# Sheet1.net
KiCad netlist of a schematic drawn in Altium Designer
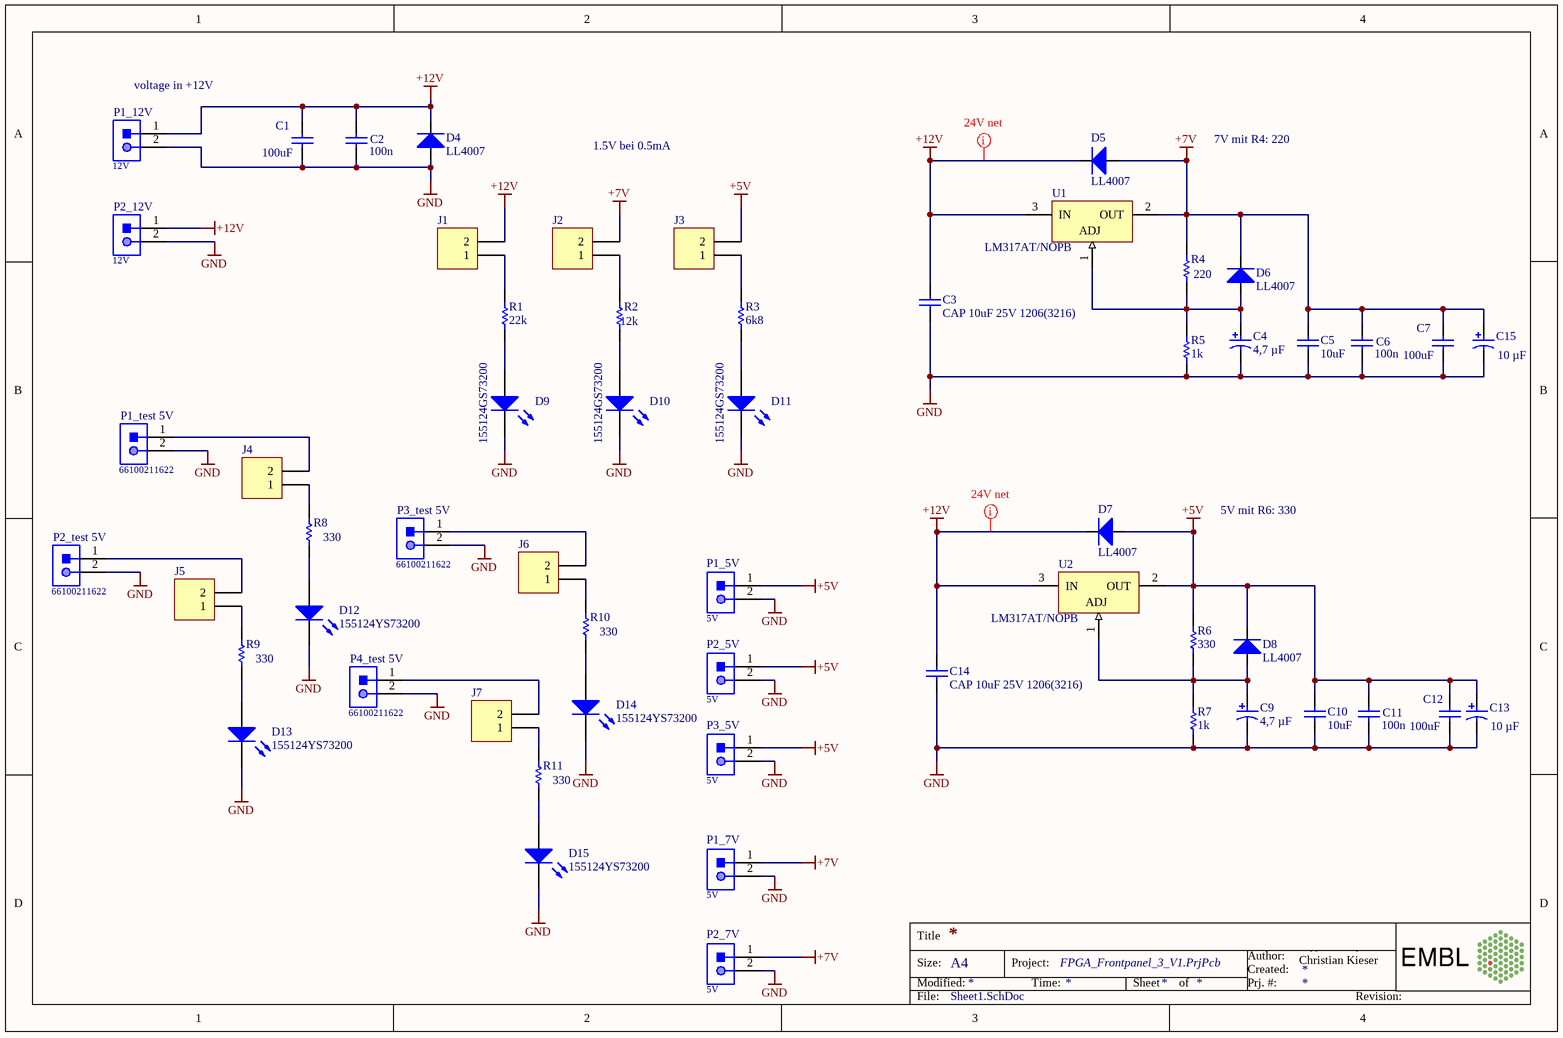
[diagram p0: Sheet1.SchDoc]

(export (version "E")
  (design (tool "Eeschema 10.0.6"))
  (components
    (comp (ref "C1")
      (value "100uF")
      (footprint "CAPC1206(3216)190_L")
      (description "CAP 100uF 6.3V ±20% 1206 (3216 Metric) Thickness 1.9mm SMD")
      (fields (field (name "TOLERANCE") "Â±20%") (field (name "PARTNUMBER") "885012108005"))
      (libsource (lib "Altium Vault EMBL 3") (part "CMP-00469-2"))
    )
    (comp (ref "C2")
      (value "100n")
      (footprint "CAPC2013X88X50ML20T25")
      (description "generic 0805 COG oder X7R Vielschichtkondensatoren max. +/-10%")
      (libsource (lib "Altium Vault EMBL 3") (part "CMP-001-0082-2"))
    )
    (comp (ref "C3")
      (value "CAP 10uF 25V 1206(3216)")
      (footprint "CAPC1206(3216)190_N")
      (description "CAP 10uF 25V -20% to +80% 1206 (3216 Metric) Thickness 1.9mm SMD")
      (fields
        (field (name "TOLERANCE") "-20% to +80%")
        (field (name "MANUFACTURER") "Wurth Electronics Inc.")
      )
      (libsource (lib "Altium Vault EMBL 3") (part "CMP-00471-2"))
    )
    (comp (ref "C4")
      (value "4,7 µF")
      (footprint "A Package")
      (description "4,7 µF; 6V; Gr. A; T491A475K006AT")
      (fields (field (name "MANUFACTURER") "KEMET") (field (name "TOLERANCE") "±10%"))
      (libsource (lib "EMBL") (part "CAP-P-2"))
    )
    (comp (ref "C5")
      (value "10uF")
      (footprint "CAPC1206(3216)190_N")
      (description "CAP 10uF 25V -20% to +80% 1206 (3216 Metric) Thickness 1.9mm SMD")
      (fields
        (field (name "TOLERANCE") "-20% to +80%")
        (field (name "MANUFACTURER") "Wurth Electronics Inc.")
      )
      (libsource (lib "Altium Vault EMBL 3") (part "CMP-00471-2"))
    )
    (comp (ref "C6")
      (value "100n")
      (footprint "CAPC2013X88X50ML20T25")
      (description "generic 0805 COG oder X7R Vielschichtkondensatoren max. +/-10%")
      (libsource (lib "Altium Vault EMBL 3") (part "CMP-001-0082-2"))
    )
    (comp (ref "C7")
      (value "100uF")
      (footprint "CAPC1206(3216)190_L")
      (description "CAP 100uF 6.3V ±20% 1206 (3216 Metric) Thickness 1.9mm SMD")
      (fields (field (name "TOLERANCE") "Â±20%") (field (name "PARTNUMBER") "885012108005"))
      (libsource (lib "Altium Vault EMBL 3") (part "CMP-00469-2"))
    )
    (comp (ref "C9")
      (value "4,7 µF")
      (footprint "A Package")
      (description "4,7 µF; 6V; Gr. A; T491A475K006AT")
      (fields (field (name "MANUFACTURER") "KEMET") (field (name "TOLERANCE") "±10%"))
      (libsource (lib "Altium Vault EMBL 3") (part "CMP-001-0039-3"))
    )
    (comp (ref "C10")
      (value "10uF")
      (footprint "CAPC1206(3216)190_N")
      (description "CAP 10uF 25V -20% to +80% 1206 (3216 Metric) Thickness 1.9mm SMD")
      (fields
        (field (name "TOLERANCE") "-20% to +80%")
        (field (name "MANUFACTURER") "Wurth Electronics Inc.")
      )
      (libsource (lib "Altium Vault EMBL 3") (part "CMP-00471-2"))
    )
    (comp (ref "C11")
      (value "100n")
      (footprint "CAPC2013X88X50ML20T25")
      (description "generic 0805 COG oder X7R Vielschichtkondensatoren max. +/-10%")
      (libsource (lib "Altium Vault EMBL 3") (part "CMP-001-0082-2"))
    )
    (comp (ref "C12")
      (value "100uF")
      (footprint "CAPC1206(3216)190_L")
      (description "CAP 100uF 6.3V ±20% 1206 (3216 Metric) Thickness 1.9mm SMD")
      (fields (field (name "TOLERANCE") "Â±20%") (field (name "PARTNUMBER") "885012108005"))
      (libsource (lib "Altium Vault EMBL 3") (part "CMP-00469-2"))
    )
    (comp (ref "C13")
      (value "10 µF")
      (footprint "KEMT-520-D_Low")
      (description "10 µF, 35V, 125 mOhm, Gr. D\npartnumb: T495D106K035ATE125")
      (fields (field (name "MANUFACTURER") "KEMET") (field (name "TOLERANCE") "±10%"))
      (libsource (lib "Altium Vault EMBL 3") (part "CMP-001-0033-3"))
    )
    (comp (ref "C14")
      (value "CAP 10uF 25V 1206(3216)")
      (footprint "CAPC1206(3216)190_N")
      (description "CAP 10uF 25V -20% to +80% 1206 (3216 Metric) Thickness 1.9mm SMD")
      (fields
        (field (name "TOLERANCE") "-20% to +80%")
        (field (name "MANUFACTURER") "Wurth Electronics Inc.")
      )
      (libsource (lib "Altium Vault EMBL 3") (part "CMP-00471-2"))
    )
    (comp (ref "C15")
      (value "10 µF")
      (footprint "KEMT-520-D_Low")
      (description "10 µF, 35V, 125 mOhm, Gr. D\npartnumb: T495D106K035ATE125")
      (fields (field (name "MANUFACTURER") "KEMET") (field (name "TOLERANCE") "±10%"))
      (libsource (lib "Altium Vault EMBL 3") (part "CMP-001-0033-3"))
    )
    (comp (ref "D4")
      (value "LL4007")
      (footprint "LL4007")
      (description "LL4007;  Vf 1,1V @ 1A, If = 1A")
      (fields (field (name "MANUFACTURER") "TAIWAN SEMICONDUCTOR") (field (name "PARTNUMBER") "LL4007G L2"))
      (libsource (lib "Altium Vault EMBL 3") (part "CMP-001-0049-2"))
    )
    (comp (ref "D5")
      (value "LL4007")
      (footprint "LL4007")
      (description "LL4007;  Vf 1,1V @ 1A, If = 1A")
      (fields (field (name "MANUFACTURER") "TAIWAN SEMICONDUCTOR") (field (name "PARTNUMBER") "LL4007G L2"))
      (libsource (lib "Altium Vault EMBL 3") (part "CMP-001-0049-2"))
    )
    (comp (ref "D6")
      (value "LL4007")
      (footprint "LL4007")
      (description "LL4007;  Vf 1,1V @ 1A, If = 1A")
      (fields (field (name "MANUFACTURER") "TAIWAN SEMICONDUCTOR") (field (name "PARTNUMBER") "LL4007G L2"))
      (libsource (lib "Altium Vault EMBL 3") (part "CMP-001-0049-2"))
    )
    (comp (ref "D7")
      (value "LL4007")
      (footprint "LL4007")
      (description "LL4007;  Vf 1,1V @ 1A, If = 1A")
      (fields (field (name "MANUFACTURER") "TAIWAN SEMICONDUCTOR") (field (name "PARTNUMBER") "LL4007G L2"))
      (libsource (lib "Altium Vault EMBL 3") (part "CMP-001-0049-2"))
    )
    (comp (ref "D8")
      (value "LL4007")
      (footprint "LL4007")
      (description "LL4007;  Vf 1,1V @ 1A, If = 1A")
      (fields (field (name "MANUFACTURER") "TAIWAN SEMICONDUCTOR") (field (name "PARTNUMBER") "LL4007G L2"))
      (libsource (lib "Altium Vault EMBL 3") (part "CMP-001-0049-2"))
    )
    (comp (ref "D9")
      (value "155124GS73200")
      (footprint "1204")
      (description "Single Color LED, Green, Water Clear, 2mm")
      (libsource (lib "EMBL") (part "WE-LED_K1A2-2"))
    )
    (comp (ref "D10")
      (value "155124GS73200")
      (footprint "1204")
      (description "Single Color LED, Green, Water Clear, 2mm")
      (libsource (lib "EMBL") (part "WE-LED_K1A2-2"))
    )
    (comp (ref "D11")
      (value "155124GS73200")
      (footprint "1204")
      (description "Single Color LED, Green, Water Clear, 2mm")
      (libsource (lib "EMBL") (part "WE-LED_K1A2-2"))
    )
    (comp (ref "D12")
      (value "155124YS73200")
      (footprint "1204")
      (description "Single Color LED, Yellow, Water Clear, 2mm")
      (libsource (lib "EMBL") (part "WE-LED_K1A2-2"))
    )
    (comp (ref "D13")
      (value "155124YS73200")
      (footprint "1204")
      (description "Single Color LED, Yellow, Water Clear, 2mm")
      (libsource (lib "EMBL") (part "WE-LED_K1A2-2"))
    )
    (comp (ref "D14")
      (value "155124YS73200")
      (footprint "1204")
      (description "Single Color LED, Yellow, Water Clear, 2mm")
      (libsource (lib "EMBL") (part "WE-LED_K1A2-2"))
    )
    (comp (ref "D15")
      (value "155124YS73200")
      (footprint "1204")
      (description "Single Color LED, Yellow, Water Clear, 2mm")
      (libsource (lib "EMBL") (part "WE-LED_K1A2-2"))
    )
    (comp (ref "J1")
      (value "61300211121")
      (footprint "61300211121")
      (description "2Pol; gerade; WR-PHD 2.54 mm THT Pin Header")
      (fields (field (name "MANUFACTURER") "Wurth Electronics"))
      (libsource (lib "EMBL") (part "61300211121"))
    )
    (comp (ref "J2")
      (value "61300211121")
      (footprint "61300211121")
      (description "2Pol; gerade; WR-PHD 2.54 mm THT Pin Header")
      (fields (field (name "MANUFACTURER") "Wurth Electronics"))
      (libsource (lib "EMBL") (part "61300211121"))
    )
    (comp (ref "J3")
      (value "61300211121")
      (footprint "61300211121")
      (description "2Pol; gerade; WR-PHD 2.54 mm THT Pin Header")
      (fields (field (name "MANUFACTURER") "Wurth Electronics"))
      (libsource (lib "EMBL") (part "61300211121"))
    )
    (comp (ref "J4")
      (value "61300211121")
      (footprint "61300211121")
      (description "2Pol; gerade; WR-PHD 2.54 mm THT Pin Header")
      (fields (field (name "MANUFACTURER") "Wurth Electronics"))
      (libsource (lib "EMBL") (part "61300211121"))
    )
    (comp (ref "J5")
      (value "61300211121")
      (footprint "61300211121")
      (description "2Pol; gerade; WR-PHD 2.54 mm THT Pin Header")
      (fields (field (name "MANUFACTURER") "Wurth Electronics"))
      (libsource (lib "EMBL") (part "61300211121"))
    )
    (comp (ref "J6")
      (value "61300211121")
      (footprint "61300211121")
      (description "2Pol; gerade; WR-PHD 2.54 mm THT Pin Header")
      (fields (field (name "MANUFACTURER") "Wurth Electronics"))
      (libsource (lib "EMBL") (part "61300211121"))
    )
    (comp (ref "J7")
      (value "61300211121")
      (footprint "61300211121")
      (description "2Pol; gerade; WR-PHD 2.54 mm THT Pin Header")
      (fields (field (name "MANUFACTURER") "Wurth Electronics"))
      (libsource (lib "EMBL") (part "61300211121"))
    )
    (comp (ref "P1_5V")
      (value "5V")
      (footprint "66100211622")
      (description "WR-WTB 2.54 mm Male Vertical Shrouded Header 2 Pins")
      (fields (field (name "PARTNUMBER") "66100211622") (field (name "MANUFACTURER") "Wurth Electronics"))
      (libsource (lib "EMBL") (part "WE-CN-1P-M-R2"))
    )
    (comp (ref "P1_7V")
      (value "5V")
      (footprint "66100211622")
      (description "WR-WTB 2.54 mm Male Vertical Shrouded Header 2 Pins")
      (fields (field (name "PARTNUMBER") "66100211622") (field (name "MANUFACTURER") "Wurth Electronics"))
      (libsource (lib "EMBL") (part "WE-CN-1P-M-R2"))
    )
    (comp (ref "P1_12V")
      (value "12V")
      (footprint "66100211622")
      (description "WR-WTB 2.54 mm Male Vertical Shrouded Header 2 Pins")
      (fields (field (name "PARTNUMBER") "66100211622") (field (name "MANUFACTURER") "Wurth Electronics"))
      (libsource (lib "EMBL") (part "WE-CN-1P-M-R2"))
    )
    (comp (ref "P1_test 5V")
      (value "66100211622")
      (footprint "66100211622")
      (description "WR-WTB 2.54 mm Male Vertical Shrouded Header 2 Pins")
      (fields (field (name "MANUFACTURER") "Wurth Electronics"))
      (libsource (lib "EMBL") (part "WE-CN-1P-M-R2"))
    )
    (comp (ref "P2_5V")
      (value "5V")
      (footprint "66100211622")
      (description "WR-WTB 2.54 mm Male Vertical Shrouded Header 2 Pins")
      (fields (field (name "PARTNUMBER") "66100211622") (field (name "MANUFACTURER") "Wurth Electronics"))
      (libsource (lib "EMBL") (part "WE-CN-1P-M-R2"))
    )
    (comp (ref "P2_7V")
      (value "5V")
      (footprint "66100211622")
      (description "WR-WTB 2.54 mm Male Vertical Shrouded Header 2 Pins")
      (fields (field (name "PARTNUMBER") "66100211622") (field (name "MANUFACTURER") "Wurth Electronics"))
      (libsource (lib "EMBL") (part "WE-CN-1P-M-R2"))
    )
    (comp (ref "P2_12V")
      (value "12V")
      (footprint "66100211622")
      (description "WR-WTB 2.54 mm Male Vertical Shrouded Header 2 Pins")
      (fields (field (name "PARTNUMBER") "66100211622") (field (name "MANUFACTURER") "Wurth Electronics"))
      (libsource (lib "EMBL") (part "WE-CN-1P-M-R2"))
    )
    (comp (ref "P2_test 5V")
      (value "66100211622")
      (footprint "66100211622")
      (description "WR-WTB 2.54 mm Male Vertical Shrouded Header 2 Pins")
      (fields (field (name "MANUFACTURER") "Wurth Electronics"))
      (libsource (lib "EMBL") (part "WE-CN-1P-M-R2"))
    )
    (comp (ref "P3_5V")
      (value "5V")
      (footprint "66100211622")
      (description "WR-WTB 2.54 mm Male Vertical Shrouded Header 2 Pins")
      (fields (field (name "PARTNUMBER") "66100211622") (field (name "MANUFACTURER") "Wurth Electronics"))
      (libsource (lib "EMBL") (part "WE-CN-1P-M-R2"))
    )
    (comp (ref "P3_test 5V")
      (value "66100211622")
      (footprint "66100211622")
      (description "WR-WTB 2.54 mm Male Vertical Shrouded Header 2 Pins")
      (fields (field (name "MANUFACTURER") "Wurth Electronics"))
      (libsource (lib "EMBL") (part "WE-CN-1P-M-R2"))
    )
    (comp (ref "P4_test 5V")
      (value "66100211622")
      (footprint "66100211622")
      (description "WR-WTB 2.54 mm Male Vertical Shrouded Header 2 Pins")
      (fields (field (name "MANUFACTURER") "Wurth Electronics"))
      (libsource (lib "EMBL") (part "WE-CN-1P-M-R2"))
    )
    (comp (ref "R1")
      (value "22k")
      (footprint "YAGO-RC0805_M")
      (description "0805 Yageo Standard BlackBox Resistors")
      (fields (field (name "TOLERANCE") "±1%") (field (name "MANUFACTURER") "Yageo"))
      (libsource (lib "Altium Vault EMBL") (part "0805"))
    )
    (comp (ref "R2")
      (value "12k")
      (footprint "YAGO-RC0805_M")
      (description "0805 Yageo Standard BlackBox Resistors")
      (fields (field (name "TOLERANCE") "±1%") (field (name "MANUFACTURER") "Yageo"))
      (libsource (lib "Altium Vault EMBL") (part "0805"))
    )
    (comp (ref "R3")
      (value "6k8")
      (footprint "YAGO-RC0805_M")
      (description "0805 Yageo Standard BlackBox Resistors")
      (fields (field (name "TOLERANCE") "±1%") (field (name "MANUFACTURER") "Yageo"))
      (libsource (lib "Altium Vault EMBL") (part "0805"))
    )
    (comp (ref "R4")
      (value "220")
      (footprint "YAGO-RC0805_M")
      (description "0805 Yageo Standard BlackBox Resistors")
      (fields (field (name "TOLERANCE") "±1%") (field (name "MANUFACTURER") "Yageo"))
      (libsource (lib "Altium Vault EMBL") (part "0805"))
    )
    (comp (ref "R5")
      (value "1k")
      (footprint "YAGO-RC0805_M")
      (description "0805 Yageo Standard BlackBox Resistors")
      (fields (field (name "TOLERANCE") "±1%") (field (name "MANUFACTURER") "Yageo"))
      (libsource (lib "Altium Vault EMBL") (part "0805"))
    )
    (comp (ref "R6")
      (value "330")
      (footprint "YAGO-RC0805_M")
      (description "0805 Yageo Standard BlackBox Resistors")
      (fields (field (name "TOLERANCE") "±1%") (field (name "MANUFACTURER") "Yageo"))
      (libsource (lib "Altium Vault EMBL") (part "0805"))
    )
    (comp (ref "R7")
      (value "1k")
      (footprint "YAGO-RC0805_M")
      (description "0805 Yageo Standard BlackBox Resistors")
      (fields (field (name "TOLERANCE") "±1%") (field (name "MANUFACTURER") "Yageo"))
      (libsource (lib "Altium Vault EMBL") (part "0805"))
    )
    (comp (ref "R8")
      (value "330")
      (footprint "YAGO-RC0805_M")
      (description "0805 Yageo Standard BlackBox Resistors")
      (fields (field (name "TOLERANCE") "±1%") (field (name "MANUFACTURER") "Yageo"))
      (libsource (lib "Altium Vault EMBL") (part "0805"))
    )
    (comp (ref "R9")
      (value "330")
      (footprint "YAGO-RC0805_M")
      (description "0805 Yageo Standard BlackBox Resistors")
      (fields (field (name "TOLERANCE") "±1%") (field (name "MANUFACTURER") "Yageo"))
      (libsource (lib "Altium Vault EMBL") (part "0805"))
    )
    (comp (ref "R10")
      (value "330")
      (footprint "YAGO-RC0805_M")
      (description "0805 Yageo Standard BlackBox Resistors")
      (fields (field (name "TOLERANCE") "±1%") (field (name "MANUFACTURER") "Yageo"))
      (libsource (lib "Altium Vault EMBL") (part "0805"))
    )
    (comp (ref "R11")
      (value "330")
      (footprint "YAGO-RC0805_M")
      (description "0805 Yageo Standard BlackBox Resistors")
      (fields (field (name "TOLERANCE") "±1%") (field (name "MANUFACTURER") "Yageo"))
      (libsource (lib "Altium Vault EMBL") (part "0805"))
    )
    (comp (ref "U1")
      (value "LM317AT/NOPB")
      (footprint "NDE0003A")
      (description "3-Terminal Adjustable Regulator, 3-pin TO-220, Pb-Free")
      (fields (field (name "MANUFACTURER") "Texas Instruments"))
      (libsource (lib "Altium Vault EMBL 3") (part "CMP-00535-1"))
    )
    (comp (ref "U2")
      (value "LM317AT/NOPB")
      (footprint "NDE0003A")
      (description "3-Terminal Adjustable Regulator, 3-pin TO-220, Pb-Free")
      (fields (field (name "MANUFACTURER") "Texas Instruments"))
      (libsource (lib "Altium Vault EMBL 3") (part "CMP-00535-1"))
    )
  )
  (nets
    (net (code "1") (name "+5V") (class "Default")
      (node (ref "C10") (pin "2") (pinfunction "2_2") (pintype "passive"))
      (node (ref "C11") (pin "2") (pinfunction "2_2") (pintype "passive"))
      (node (ref "C12") (pin "2") (pinfunction "2_2") (pintype "passive"))
      (node (ref "C13") (pin "1") (pinfunction "1_1") (pintype "passive"))
      (node (ref "D7") (pin "1") (pinfunction "A_1") (pintype "passive"))
      (node (ref "D8") (pin "2") (pinfunction "K_2") (pintype "passive"))
      (node (ref "J3") (pin "2") (pinfunction "2_2") (pintype "passive"))
      (node (ref "P1_5V") (pin "1") (pinfunction "1_1") (pintype "passive"))
      (node (ref "P2_5V") (pin "1") (pinfunction "1_1") (pintype "passive"))
      (node (ref "P3_5V") (pin "1") (pinfunction "1_1") (pintype "passive"))
      (node (ref "R6") (pin "2") (pinfunction "2_2") (pintype "passive"))
      (node (ref "U2") (pin "2") (pinfunction "OUT_2") (pintype "power_in"))
    )
    (net (code "2") (name "+7V") (class "Default")
      (node (ref "C15") (pin "1") (pinfunction "1_1") (pintype "passive"))
      (node (ref "C5") (pin "2") (pinfunction "2_2") (pintype "passive"))
      (node (ref "C6") (pin "2") (pinfunction "2_2") (pintype "passive"))
      (node (ref "C7") (pin "2") (pinfunction "2_2") (pintype "passive"))
      (node (ref "D5") (pin "1") (pinfunction "A_1") (pintype "passive"))
      (node (ref "D6") (pin "2") (pinfunction "K_2") (pintype "passive"))
      (node (ref "J2") (pin "2") (pinfunction "2_2") (pintype "passive"))
      (node (ref "P1_7V") (pin "1") (pinfunction "1_1") (pintype "passive"))
      (node (ref "P2_7V") (pin "1") (pinfunction "1_1") (pintype "passive"))
      (node (ref "R4") (pin "2") (pinfunction "2_2") (pintype "passive"))
      (node (ref "U1") (pin "2") (pinfunction "OUT_2") (pintype "power_in"))
    )
    (net (code "3") (name "+12V") (class "Default")
      (node (ref "C1") (pin "2") (pinfunction "2_2") (pintype "passive"))
      (node (ref "C14") (pin "2") (pinfunction "2_2") (pintype "passive"))
      (node (ref "C2") (pin "2") (pinfunction "2_2") (pintype "passive"))
      (node (ref "C3") (pin "2") (pinfunction "2_2") (pintype "passive"))
      (node (ref "D4") (pin "2") (pinfunction "K_2") (pintype "passive"))
      (node (ref "D5") (pin "2") (pinfunction "K_2") (pintype "passive"))
      (node (ref "D7") (pin "2") (pinfunction "K_2") (pintype "passive"))
      (node (ref "J1") (pin "2") (pinfunction "2_2") (pintype "passive"))
      (node (ref "P1_12V") (pin "1") (pinfunction "1_1") (pintype "passive"))
      (node (ref "P2_12V") (pin "1") (pinfunction "1_1") (pintype "passive"))
      (node (ref "U1") (pin "3") (pinfunction "IN_3") (pintype "power_in"))
      (node (ref "U2") (pin "3") (pinfunction "IN_3") (pintype "power_in"))
    )
    (net (code "4") (name "GND") (class "Default")
      (node (ref "C1") (pin "1") (pinfunction "1_1") (pintype "passive"))
      (node (ref "C10") (pin "1") (pinfunction "1_1") (pintype "passive"))
      (node (ref "C11") (pin "1") (pinfunction "1_1") (pintype "passive"))
      (node (ref "C12") (pin "1") (pinfunction "1_1") (pintype "passive"))
      (node (ref "C13") (pin "2") (pinfunction "2_2") (pintype "passive"))
      (node (ref "C14") (pin "1") (pinfunction "1_1") (pintype "passive"))
      (node (ref "C15") (pin "2") (pinfunction "2_2") (pintype "passive"))
      (node (ref "C2") (pin "1") (pinfunction "1_1") (pintype "passive"))
      (node (ref "C3") (pin "1") (pinfunction "1_1") (pintype "passive"))
      (node (ref "C4") (pin "2") (pinfunction "2_2") (pintype "passive"))
      (node (ref "C5") (pin "1") (pinfunction "1_1") (pintype "passive"))
      (node (ref "C6") (pin "1") (pinfunction "1_1") (pintype "passive"))
      (node (ref "C7") (pin "1") (pinfunction "1_1") (pintype "passive"))
      (node (ref "C9") (pin "2") (pinfunction "2_2") (pintype "passive"))
      (node (ref "D10") (pin "1") (pinfunction "K_1") (pintype "passive"))
      (node (ref "D11") (pin "1") (pinfunction "K_1") (pintype "passive"))
      (node (ref "D12") (pin "1") (pinfunction "K_1") (pintype "passive"))
      (node (ref "D13") (pin "1") (pinfunction "K_1") (pintype "passive"))
      (node (ref "D14") (pin "1") (pinfunction "K_1") (pintype "passive"))
      (node (ref "D15") (pin "1") (pinfunction "K_1") (pintype "passive"))
      (node (ref "D4") (pin "1") (pinfunction "A_1") (pintype "passive"))
      (node (ref "D9") (pin "1") (pinfunction "K_1") (pintype "passive"))
      (node (ref "P1_12V") (pin "2") (pinfunction "2_2") (pintype "passive"))
      (node (ref "P1_5V") (pin "2") (pinfunction "2_2") (pintype "passive"))
      (node (ref "P1_7V") (pin "2") (pinfunction "2_2") (pintype "passive"))
      (node (ref "P1_test 5V") (pin "2") (pinfunction "2_2") (pintype "passive"))
      (node (ref "P2_12V") (pin "2") (pinfunction "2_2") (pintype "passive"))
      (node (ref "P2_5V") (pin "2") (pinfunction "2_2") (pintype "passive"))
      (node (ref "P2_7V") (pin "2") (pinfunction "2_2") (pintype "passive"))
      (node (ref "P2_test 5V") (pin "2") (pinfunction "2_2") (pintype "passive"))
      (node (ref "P3_5V") (pin "2") (pinfunction "2_2") (pintype "passive"))
      (node (ref "P3_test 5V") (pin "2") (pinfunction "2_2") (pintype "passive"))
      (node (ref "P4_test 5V") (pin "2") (pinfunction "2_2") (pintype "passive"))
      (node (ref "R5") (pin "1") (pinfunction "1_1") (pintype "passive"))
      (node (ref "R7") (pin "1") (pinfunction "1_1") (pintype "passive"))
    )
    (net (code "5") (name "Net-(D6-A)") (class "Default")
      (node (ref "C4") (pin "1") (pinfunction "1_1") (pintype "passive"))
      (node (ref "D6") (pin "1") (pinfunction "A_1") (pintype "passive"))
      (node (ref "R4") (pin "1") (pinfunction "1_1") (pintype "passive"))
      (node (ref "R5") (pin "2") (pinfunction "2_2") (pintype "passive"))
      (node (ref "U1") (pin "1") (pinfunction "ADJ_1") (pintype "input"))
    )
    (net (code "6") (name "Net-(D8-A)") (class "Default")
      (node (ref "C9") (pin "1") (pinfunction "1_1") (pintype "passive"))
      (node (ref "D8") (pin "1") (pinfunction "A_1") (pintype "passive"))
      (node (ref "R6") (pin "1") (pinfunction "1_1") (pintype "passive"))
      (node (ref "R7") (pin "2") (pinfunction "2_2") (pintype "passive"))
      (node (ref "U2") (pin "1") (pinfunction "ADJ_1") (pintype "input"))
    )
    (net (code "7") (name "Net-(D9-A)") (class "Default")
      (node (ref "D9") (pin "2") (pinfunction "A_2") (pintype "passive"))
      (node (ref "R1") (pin "1") (pinfunction "1_1") (pintype "passive"))
    )
    (net (code "8") (name "Net-(D10-A)") (class "Default")
      (node (ref "D10") (pin "2") (pinfunction "A_2") (pintype "passive"))
      (node (ref "R2") (pin "1") (pinfunction "1_1") (pintype "passive"))
    )
    (net (code "9") (name "Net-(D11-A)") (class "Default")
      (node (ref "D11") (pin "2") (pinfunction "A_2") (pintype "passive"))
      (node (ref "R3") (pin "1") (pinfunction "1_1") (pintype "passive"))
    )
    (net (code "10") (name "Net-(D12-A)") (class "Default")
      (node (ref "D12") (pin "2") (pinfunction "A_2") (pintype "passive"))
      (node (ref "R8") (pin "1") (pinfunction "1_1") (pintype "passive"))
    )
    (net (code "11") (name "Net-(D13-A)") (class "Default")
      (node (ref "D13") (pin "2") (pinfunction "A_2") (pintype "passive"))
      (node (ref "R9") (pin "1") (pinfunction "1_1") (pintype "passive"))
    )
    (net (code "12") (name "Net-(D14-A)") (class "Default")
      (node (ref "D14") (pin "2") (pinfunction "A_2") (pintype "passive"))
      (node (ref "R10") (pin "1") (pinfunction "1_1") (pintype "passive"))
    )
    (net (code "13") (name "Net-(D15-A)") (class "Default")
      (node (ref "D15") (pin "2") (pinfunction "A_2") (pintype "passive"))
      (node (ref "R11") (pin "1") (pinfunction "1_1") (pintype "passive"))
    )
    (net (code "14") (name "Net-(J1-Pad1)") (class "Default")
      (node (ref "J1") (pin "1") (pinfunction "1_1") (pintype "passive"))
      (node (ref "R1") (pin "2") (pinfunction "2_2") (pintype "passive"))
    )
    (net (code "15") (name "Net-(J2-Pad1)") (class "Default")
      (node (ref "J2") (pin "1") (pinfunction "1_1") (pintype "passive"))
      (node (ref "R2") (pin "2") (pinfunction "2_2") (pintype "passive"))
    )
    (net (code "16") (name "Net-(J3-Pad1)") (class "Default")
      (node (ref "J3") (pin "1") (pinfunction "1_1") (pintype "passive"))
      (node (ref "R3") (pin "2") (pinfunction "2_2") (pintype "passive"))
    )
    (net (code "17") (name "Net-(J4-Pad1)") (class "Default")
      (node (ref "J4") (pin "1") (pinfunction "1_1") (pintype "passive"))
      (node (ref "R8") (pin "2") (pinfunction "2_2") (pintype "passive"))
    )
    (net (code "18") (name "Net-(J4-Pad2)") (class "Default")
      (node (ref "J4") (pin "2") (pinfunction "2_2") (pintype "passive"))
      (node (ref "P1_test 5V") (pin "1") (pinfunction "1_1") (pintype "passive"))
    )
    (net (code "19") (name "Net-(J5-Pad1)") (class "Default")
      (node (ref "J5") (pin "1") (pinfunction "1_1") (pintype "passive"))
      (node (ref "R9") (pin "2") (pinfunction "2_2") (pintype "passive"))
    )
    (net (code "20") (name "Net-(J5-Pad2)") (class "Default")
      (node (ref "J5") (pin "2") (pinfunction "2_2") (pintype "passive"))
      (node (ref "P2_test 5V") (pin "1") (pinfunction "1_1") (pintype "passive"))
    )
    (net (code "21") (name "Net-(J6-Pad1)") (class "Default")
      (node (ref "J6") (pin "1") (pinfunction "1_1") (pintype "passive"))
      (node (ref "R10") (pin "2") (pinfunction "2_2") (pintype "passive"))
    )
    (net (code "22") (name "Net-(J6-Pad2)") (class "Default")
      (node (ref "J6") (pin "2") (pinfunction "2_2") (pintype "passive"))
      (node (ref "P3_test 5V") (pin "1") (pinfunction "1_1") (pintype "passive"))
    )
    (net (code "23") (name "Net-(J7-Pad1)") (class "Default")
      (node (ref "J7") (pin "1") (pinfunction "1_1") (pintype "passive"))
      (node (ref "R11") (pin "2") (pinfunction "2_2") (pintype "passive"))
    )
    (net (code "24") (name "Net-(J7-Pad2)") (class "Default")
      (node (ref "J7") (pin "2") (pinfunction "2_2") (pintype "passive"))
      (node (ref "P4_test 5V") (pin "1") (pinfunction "1_1") (pintype "passive"))
    )
  )
)
